# power.net
KiCad netlist of a schematic drawn in Altium Designer
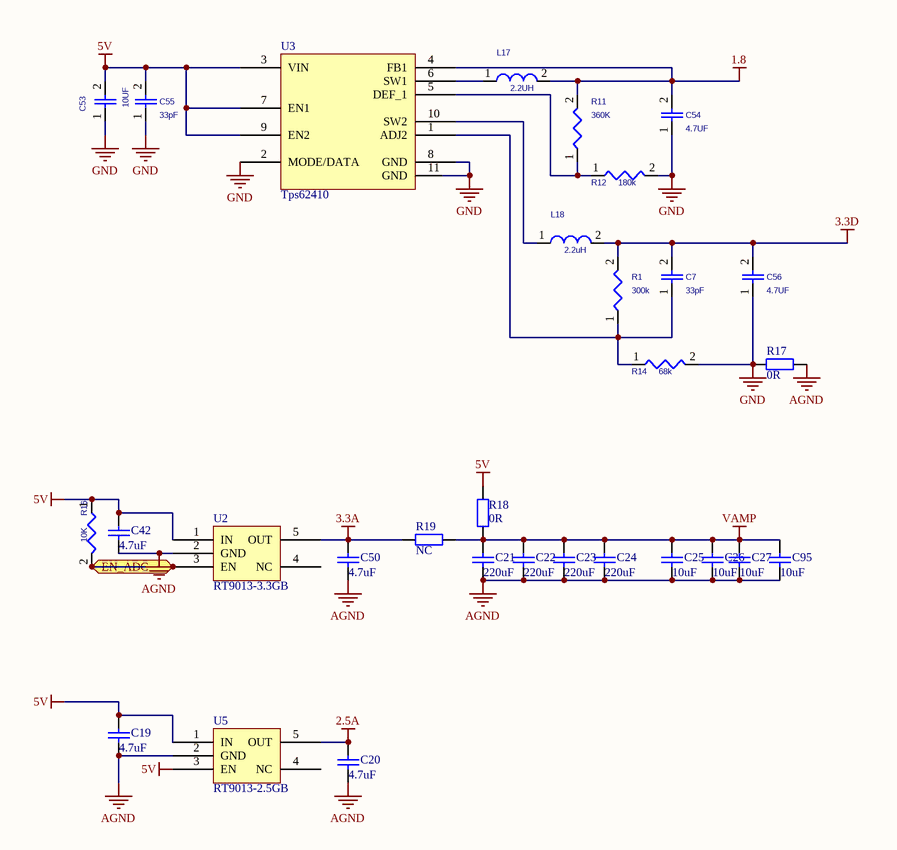
[diagram p0: power.SchDoc]

(export (version "E")
  (design (tool "Eeschema 10.0.6"))
  (components
    (comp (ref "C7") (value "33pF") (footprint "0402") (libsource (lib "*") (part "CAP/0402")))
    (comp (ref "C19")
      (value "4.7uF")
      (footprint "0603")
      (description "Capacitor")
      (fields (field (name "PUBLISHER") "Altium Limited"))
      (libsource (lib "RTC6705") (part "Cap"))
    )
    (comp (ref "C20")
      (value "4.7uF")
      (footprint "0603")
      (description "Capacitor")
      (fields (field (name "PUBLISHER") "Altium Limited"))
      (libsource (lib "RTC6705") (part "Cap"))
    )
    (comp (ref "C21")
      (value "220uF")
      (footprint "1210")
      (description "Capacitor")
      (fields (field (name "PUBLISHER") "Altium Limited"))
      (libsource (lib "RTC6705") (part "Cap"))
    )
    (comp (ref "C22")
      (value "220uF")
      (footprint "1210")
      (description "Capacitor")
      (fields (field (name "PUBLISHER") "Altium Limited"))
      (libsource (lib "RTC6705") (part "Cap"))
    )
    (comp (ref "C23")
      (value "220uF")
      (footprint "1210")
      (description "Capacitor")
      (fields (field (name "PUBLISHER") "Altium Limited"))
      (libsource (lib "RTC6705") (part "Cap"))
    )
    (comp (ref "C24")
      (value "220uF")
      (footprint "1210")
      (description "Capacitor")
      (fields (field (name "PUBLISHER") "Altium Limited"))
      (libsource (lib "RTC6705") (part "Cap"))
    )
    (comp (ref "C25")
      (value "10uF")
      (footprint "0805")
      (description "Capacitor")
      (fields (field (name "PUBLISHER") "Altium Limited"))
      (libsource (lib "RTC6705") (part "Cap"))
    )
    (comp (ref "C26")
      (value "10uF")
      (footprint "0805")
      (description "Capacitor")
      (fields (field (name "PUBLISHER") "Altium Limited"))
      (libsource (lib "RTC6705") (part "Cap"))
    )
    (comp (ref "C27")
      (value "10uF")
      (footprint "0805")
      (description "Capacitor")
      (fields (field (name "PUBLISHER") "Altium Limited"))
      (libsource (lib "RTC6705") (part "Cap"))
    )
    (comp (ref "C42")
      (value "4.7uF")
      (footprint "0603")
      (description "Capacitor")
      (fields (field (name "PUBLISHER") "Altium Limited"))
      (libsource (lib "RTC6705") (part "Cap"))
    )
    (comp (ref "C50")
      (value "4.7uF")
      (footprint "0603")
      (description "Capacitor")
      (fields (field (name "PUBLISHER") "Altium Limited"))
      (libsource (lib "RTC6705") (part "Cap"))
    )
    (comp (ref "C53") (value "10UF") (footprint "0805") (libsource (lib "*") (part "CAP/0402")))
    (comp (ref "C54") (value "4.7UF") (footprint "0805") (libsource (lib "*") (part "CAP/0402")))
    (comp (ref "C55") (value "33pF") (footprint "0603") (libsource (lib "*") (part "CAP/0402")))
    (comp (ref "C56") (value "4.7UF") (footprint "0805") (libsource (lib "*") (part "CAP/0402")))
    (comp (ref "C95")
      (value "10uF")
      (footprint "0805")
      (description "Capacitor")
      (fields (field (name "PUBLISHER") "Altium Limited"))
      (libsource (lib "RTC6705") (part "Cap"))
    )
    (comp (ref "L17") (value "2.2UH") (footprint "0806") (libsource (lib "*") (part "L/2.5*2.0")))
    (comp (ref "L18") (value "2.2uH") (footprint "0806") (libsource (lib "*") (part "L/2.5*2.0")))
    (comp (ref "R1") (value "300k") (footprint "0402") (libsource (lib "*") (part "RES/0402_3")))
    (comp (ref "R11") (value "360K") (footprint "0402") (libsource (lib "*") (part "RES/0402_3")))
    (comp (ref "R12") (value "180k") (footprint "0402") (libsource (lib "*") (part "RES/0402_3")))
    (comp (ref "R14") (value "68k") (footprint "0402") (libsource (lib "*") (part "RES/0402_3")))
    (comp (ref "R16") (value "10K") (footprint "0402") (libsource (lib "*") (part "RES/0402_3")))
    (comp (ref "R17")
      (value "0R")
      (footprint "0603")
      (description "Resistor")
      (fields (field (name "PUBLISHER") "Altium Limited"))
      (libsource (lib "") (part "Res2_1"))
    )
    (comp (ref "R18")
      (value "0R")
      (footprint "0603")
      (description "Resistor")
      (fields (field (name "PUBLISHER") "Altium Limited"))
      (libsource (lib "RTC6705") (part "Res2"))
    )
    (comp (ref "R19")
      (value "NC")
      (footprint "0603")
      (description "Resistor")
      (fields (field (name "PUBLISHER") "Altium Limited"))
      (libsource (lib "") (part "Res2_2"))
    )
    (comp (ref "U2") (value "RT9013-3.3GB") (footprint "SOT23-5") (libsource (lib "RTC6705") (part "LP5907")))
    (comp (ref "U3") (value "Tps62410") (footprint "DFN-10P-3X3") (libsource (lib "Euler") (part "Tps62410")))
    (comp (ref "U5") (value "RT9013-2.5GB") (footprint "SOT23-5") (libsource (lib "RTC6705") (part "LP5907")))
  )
  (nets
    (net (code "1") (name "/EN_ADC") (class "Default")
      (node (ref "R16") (pin "2") (pinfunction "2_2") (pintype "passive"))
      (node (ref "U2") (pin "3") (pinfunction "EN_3") (pintype "passive"))
    )
    (net (code "2") (name "1.8") (class "Default")
      (node (ref "C54") (pin "2") (pinfunction "2_2") (pintype "passive"))
      (node (ref "L17") (pin "2") (pinfunction "2_2") (pintype "passive"))
      (node (ref "R11") (pin "2") (pinfunction "2_2") (pintype "passive"))
      (node (ref "U3") (pin "4") (pinfunction "FB1_4") (pintype "passive"))
    )
    (net (code "3") (name "2.5A") (class "Default")
      (node (ref "C20") (pin "2") (pinfunction "2_2") (pintype "passive"))
      (node (ref "U5") (pin "5") (pinfunction "OUT_5") (pintype "passive"))
    )
    (net (code "4") (name "3.3A") (class "Default")
      (node (ref "C50") (pin "2") (pinfunction "2_2") (pintype "passive"))
      (node (ref "R19") (pin "1") (pinfunction "1_1") (pintype "passive"))
      (node (ref "U2") (pin "5") (pinfunction "OUT_5") (pintype "passive"))
    )
    (net (code "5") (name "3.3D") (class "Default")
      (node (ref "C56") (pin "2") (pinfunction "2_2") (pintype "passive"))
      (node (ref "C7") (pin "2") (pinfunction "2_2") (pintype "passive"))
      (node (ref "L18") (pin "2") (pinfunction "2_2") (pintype "passive"))
      (node (ref "R1") (pin "2") (pinfunction "2_2") (pintype "passive"))
    )
    (net (code "6") (name "5V") (class "Default")
      (node (ref "C19") (pin "2") (pinfunction "2_2") (pintype "passive"))
      (node (ref "C42") (pin "2") (pinfunction "2_2") (pintype "passive"))
      (node (ref "C53") (pin "2") (pinfunction "2_2") (pintype "passive"))
      (node (ref "C55") (pin "2") (pinfunction "2_2") (pintype "passive"))
      (node (ref "R16") (pin "1") (pinfunction "1_1") (pintype "passive"))
      (node (ref "R18") (pin "2") (pinfunction "2_2") (pintype "passive"))
      (node (ref "U2") (pin "1") (pinfunction "IN_1") (pintype "passive"))
      (node (ref "U3") (pin "3") (pinfunction "VIN_3") (pintype "passive"))
      (node (ref "U3") (pin "7") (pinfunction "EN1_7") (pintype "passive"))
      (node (ref "U3") (pin "9") (pinfunction "EN2_9") (pintype "passive"))
      (node (ref "U5") (pin "1") (pinfunction "IN_1") (pintype "passive"))
      (node (ref "U5") (pin "3") (pinfunction "EN_3") (pintype "passive"))
    )
    (net (code "7") (name "AGND") (class "Default")
      (node (ref "C19") (pin "1") (pinfunction "1_1") (pintype "passive"))
      (node (ref "C20") (pin "1") (pinfunction "1_1") (pintype "passive"))
      (node (ref "C21") (pin "1") (pinfunction "1_1") (pintype "passive"))
      (node (ref "C22") (pin "1") (pinfunction "1_1") (pintype "passive"))
      (node (ref "C23") (pin "1") (pinfunction "1_1") (pintype "passive"))
      (node (ref "C24") (pin "1") (pinfunction "1_1") (pintype "passive"))
      (node (ref "C25") (pin "1") (pinfunction "1_1") (pintype "passive"))
      (node (ref "C26") (pin "1") (pinfunction "1_1") (pintype "passive"))
      (node (ref "C27") (pin "1") (pinfunction "1_1") (pintype "passive"))
      (node (ref "C42") (pin "1") (pinfunction "1_1") (pintype "passive"))
      (node (ref "C50") (pin "1") (pinfunction "1_1") (pintype "passive"))
      (node (ref "C95") (pin "1") (pinfunction "1_1") (pintype "passive"))
      (node (ref "R17") (pin "1") (pinfunction "1_1") (pintype "passive"))
      (node (ref "U2") (pin "2") (pinfunction "GND_2") (pintype "passive"))
      (node (ref "U5") (pin "2") (pinfunction "GND_2") (pintype "passive"))
    )
    (net (code "8") (name "GND") (class "Default")
      (node (ref "C53") (pin "1") (pinfunction "1_1") (pintype "passive"))
      (node (ref "C54") (pin "1") (pinfunction "1_1") (pintype "passive"))
      (node (ref "C55") (pin "1") (pinfunction "1_1") (pintype "passive"))
      (node (ref "C56") (pin "1") (pinfunction "1_1") (pintype "passive"))
      (node (ref "R12") (pin "2") (pinfunction "2_2") (pintype "passive"))
      (node (ref "R14") (pin "2") (pinfunction "2_2") (pintype "passive"))
      (node (ref "R17") (pin "2") (pinfunction "2_2") (pintype "passive"))
      (node (ref "U3") (pin "11") (pinfunction "GND_11") (pintype "passive"))
      (node (ref "U3") (pin "2") (pinfunction "MODE/DATA_2") (pintype "passive"))
      (node (ref "U3") (pin "8") (pinfunction "GND_8") (pintype "passive"))
    )
    (net (code "9") (name "Net-(U3-ADJ2)") (class "Default")
      (node (ref "C7") (pin "1") (pinfunction "1_1") (pintype "passive"))
      (node (ref "R1") (pin "1") (pinfunction "1_1") (pintype "passive"))
      (node (ref "R14") (pin "1") (pinfunction "1_1") (pintype "passive"))
      (node (ref "U3") (pin "1") (pinfunction "ADJ2_1") (pintype "passive"))
    )
    (net (code "10") (name "Net-(U3-DEF_1)") (class "Default")
      (node (ref "R11") (pin "1") (pinfunction "1_1") (pintype "passive"))
      (node (ref "R12") (pin "1") (pinfunction "1_1") (pintype "passive"))
      (node (ref "U3") (pin "5") (pinfunction "DEF_1_5") (pintype "passive"))
    )
    (net (code "11") (name "Net-(U3-SW1)") (class "Default")
      (node (ref "L17") (pin "1") (pinfunction "1_1") (pintype "passive"))
      (node (ref "U3") (pin "6") (pinfunction "SW1_6") (pintype "passive"))
    )
    (net (code "12") (name "Net-(U3-SW2)") (class "Default")
      (node (ref "L18") (pin "1") (pinfunction "1_1") (pintype "passive"))
      (node (ref "U3") (pin "10") (pinfunction "SW2_10") (pintype "passive"))
    )
    (net (code "13") (name "VAMP") (class "Default")
      (node (ref "C21") (pin "2") (pinfunction "2_2") (pintype "passive"))
      (node (ref "C22") (pin "2") (pinfunction "2_2") (pintype "passive"))
      (node (ref "C23") (pin "2") (pinfunction "2_2") (pintype "passive"))
      (node (ref "C24") (pin "2") (pinfunction "2_2") (pintype "passive"))
      (node (ref "C25") (pin "2") (pinfunction "2_2") (pintype "passive"))
      (node (ref "C26") (pin "2") (pinfunction "2_2") (pintype "passive"))
      (node (ref "C27") (pin "2") (pinfunction "2_2") (pintype "passive"))
      (node (ref "C95") (pin "2") (pinfunction "2_2") (pintype "passive"))
      (node (ref "R18") (pin "1") (pinfunction "1_1") (pintype "passive"))
      (node (ref "R19") (pin "2") (pinfunction "2_2") (pintype "passive"))
    )
    (net (code "14") (name "unconnected-(U2-NC-Pad4)") (class "Default")
      (node (ref "U2") (pin "4") (pinfunction "NC_4") (pintype "passive"))
    )
    (net (code "15") (name "unconnected-(U5-NC-Pad4)") (class "Default")
      (node (ref "U5") (pin "4") (pinfunction "NC_4") (pintype "passive"))
    )
  )
)
